# eth_100base-tx_rtl8152b.net
KiCad netlist of a schematic drawn in Altium Designer
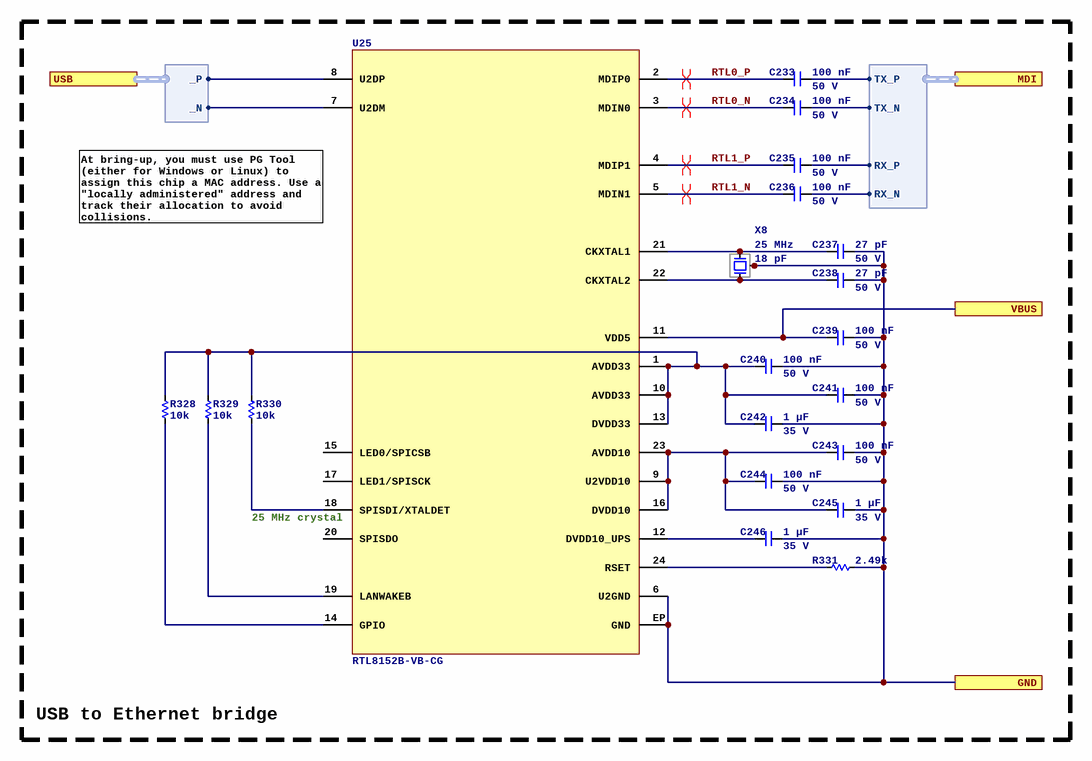
[diagram p0: eth_100base-tx_rtl8152b.SchDoc]

(export (version "E")
  (design (tool "Eeschema 10.0.6"))
  (components
    (comp (ref "C233")
      (value "CL05B104KB54PNC")
      (footprint "C0402")
      (fields
        (field (name "CAPACITANCE") "100 nF")
        (field (name "MANUFACTURER") "Samsung Electro-Mechanics")
        (field (name "VOLTAGE RATING") "50 V")
      )
      (libsource (lib "database") (part "__template_cap"))
    )
    (comp (ref "C234")
      (value "CL05B104KB54PNC")
      (footprint "C0402")
      (fields
        (field (name "CAPACITANCE") "100 nF")
        (field (name "MANUFACTURER") "Samsung Electro-Mechanics")
        (field (name "VOLTAGE RATING") "50 V")
      )
      (libsource (lib "database") (part "__template_cap"))
    )
    (comp (ref "C235")
      (value "CL05B104KB54PNC")
      (footprint "C0402")
      (fields
        (field (name "CAPACITANCE") "100 nF")
        (field (name "MANUFACTURER") "Samsung Electro-Mechanics")
        (field (name "VOLTAGE RATING") "50 V")
      )
      (libsource (lib "database") (part "__template_cap"))
    )
    (comp (ref "C236")
      (value "CL05B104KB54PNC")
      (footprint "C0402")
      (fields
        (field (name "CAPACITANCE") "100 nF")
        (field (name "MANUFACTURER") "Samsung Electro-Mechanics")
        (field (name "VOLTAGE RATING") "50 V")
      )
      (libsource (lib "database") (part "__template_cap"))
    )
    (comp (ref "C237")
      (value "CC0402JRNPO9BN270")
      (footprint "C0402")
      (fields
        (field (name "CAPACITANCE") "27 pF")
        (field (name "MANUFACTURER") "YAGEO")
        (field (name "VOLTAGE RATING") "50 V")
      )
      (libsource (lib "database") (part "__template_cap"))
    )
    (comp (ref "C238")
      (value "CC0402JRNPO9BN270")
      (footprint "C0402")
      (fields
        (field (name "CAPACITANCE") "27 pF")
        (field (name "MANUFACTURER") "YAGEO")
        (field (name "VOLTAGE RATING") "50 V")
      )
      (libsource (lib "database") (part "__template_cap"))
    )
    (comp (ref "C239")
      (value "CL05B104KB54PNC")
      (footprint "C0402")
      (fields
        (field (name "CAPACITANCE") "100 nF")
        (field (name "MANUFACTURER") "Samsung Electro-Mechanics")
        (field (name "VOLTAGE RATING") "50 V")
      )
      (libsource (lib "database") (part "__template_cap"))
    )
    (comp (ref "C240")
      (value "CL05B104KB54PNC")
      (footprint "C0402")
      (fields
        (field (name "CAPACITANCE") "100 nF")
        (field (name "MANUFACTURER") "Samsung Electro-Mechanics")
        (field (name "VOLTAGE RATING") "50 V")
      )
      (libsource (lib "database") (part "__template_cap"))
    )
    (comp (ref "C241")
      (value "CL05B104KB54PNC")
      (footprint "C0402")
      (fields
        (field (name "CAPACITANCE") "100 nF")
        (field (name "MANUFACTURER") "Samsung Electro-Mechanics")
        (field (name "VOLTAGE RATING") "50 V")
      )
      (libsource (lib "database") (part "__template_cap"))
    )
    (comp (ref "C242")
      (value "GMK107AB7105KAHT")
      (footprint "C0603")
      (fields
        (field (name "CAPACITANCE") "1 µF")
        (field (name "MANUFACTURER") "Taiyo Yuden")
        (field (name "VOLTAGE RATING") "35 V")
      )
      (libsource (lib "database") (part "__template_cap"))
    )
    (comp (ref "C243")
      (value "CL05B104KB54PNC")
      (footprint "C0402")
      (fields
        (field (name "CAPACITANCE") "100 nF")
        (field (name "MANUFACTURER") "Samsung Electro-Mechanics")
        (field (name "VOLTAGE RATING") "50 V")
      )
      (libsource (lib "database") (part "__template_cap"))
    )
    (comp (ref "C244")
      (value "CL05B104KB54PNC")
      (footprint "C0402")
      (fields
        (field (name "CAPACITANCE") "100 nF")
        (field (name "MANUFACTURER") "Samsung Electro-Mechanics")
        (field (name "VOLTAGE RATING") "50 V")
      )
      (libsource (lib "database") (part "__template_cap"))
    )
    (comp (ref "C245")
      (value "GMK107AB7105KAHT")
      (footprint "C0603")
      (fields
        (field (name "CAPACITANCE") "1 µF")
        (field (name "MANUFACTURER") "Taiyo Yuden")
        (field (name "VOLTAGE RATING") "35 V")
      )
      (libsource (lib "database") (part "__template_cap"))
    )
    (comp (ref "C246")
      (value "GMK107AB7105KAHT")
      (footprint "C0603")
      (fields
        (field (name "CAPACITANCE") "1 µF")
        (field (name "MANUFACTURER") "Taiyo Yuden")
        (field (name "VOLTAGE RATING") "35 V")
      )
      (libsource (lib "database") (part "__template_cap"))
    )
    (comp (ref "R328")
      (value "10k")
      (footprint "R0402")
      (fields
        (field (name "TOLERANCE") "1%")
        (field (name "MANUFACTURER PART NUMBER") "0402WGF1002TCE")
        (field (name "MANUFACTURER") "UNI-ROYAL(Uniroyal Elec)")
      )
      (libsource (lib "database") (part "__template_resistor"))
    )
    (comp (ref "R329")
      (value "10k")
      (footprint "R0402")
      (fields
        (field (name "TOLERANCE") "1%")
        (field (name "MANUFACTURER PART NUMBER") "0402WGF1002TCE")
        (field (name "MANUFACTURER") "UNI-ROYAL(Uniroyal Elec)")
      )
      (libsource (lib "database") (part "__template_resistor"))
    )
    (comp (ref "R330")
      (value "10k")
      (footprint "R0402")
      (fields
        (field (name "TOLERANCE") "1%")
        (field (name "MANUFACTURER PART NUMBER") "0402WGF1002TCE")
        (field (name "MANUFACTURER") "UNI-ROYAL(Uniroyal Elec)")
      )
      (libsource (lib "database") (part "__template_resistor"))
    )
    (comp (ref "R331")
      (value "2.49k")
      (footprint "R0402")
      (fields
        (field (name "TOLERANCE") "1%")
        (field (name "MANUFACTURER PART NUMBER") "0402WGF2491TCE")
        (field (name "MANUFACTURER") "UNI-ROYAL(Uniroyal Elec)")
      )
      (libsource (lib "database") (part "__template_resistor"))
    )
    (comp (ref "U25")
      (value "RTL8152B-VB-CG")
      (footprint "24QFN4E")
      (description "Integrated 10/100M Ethernet Controller for USB Applications")
      (fields (field (name "MANUFACTURER") "REALTEK"))
      (libsource (lib "database") (part "RTL8152B-VB-CG"))
    )
    (comp (ref "X8")
      (value "ECS-250-18-33-JGN-TR3")
      (footprint "4_SMD_3.2X2.5MM")
      (description "25 MHz ±20ppm Crystal 18pF 40 Ohms 4-SMD, No Lead")
      (fields
        (field (name "MANUFACTURER") "ECS Inc.")
        (field (name "FREQUENCY") "25 MHz")
        (field (name "CAPACITANCE") "18 pF")
      )
      (libsource (lib "database") (part "__template_crystal_4pin"))
    )
  )
  (nets
    (net (code "3") (name "/GND") (class "Default")
      (node (ref "C237") (pin "2") (pintype "passive"))
      (node (ref "C238") (pin "2") (pintype "passive"))
      (node (ref "C239") (pin "1") (pintype "passive"))
      (node (ref "C240") (pin "1") (pintype "passive"))
      (node (ref "C241") (pin "1") (pintype "passive"))
      (node (ref "C242") (pin "2") (pintype "passive"))
      (node (ref "C243") (pin "1") (pintype "passive"))
      (node (ref "C244") (pin "1") (pintype "passive"))
      (node (ref "C245") (pin "2") (pintype "passive"))
      (node (ref "C246") (pin "2") (pintype "passive"))
      (node (ref "R331") (pin "1") (pintype "passive"))
      (node (ref "U25") (pin "6") (pinfunction "U2GND_6") (pintype "passive"))
      (node (ref "U25") (pin "EP") (pinfunction "GND_EP") (pintype "passive"))
      (node (ref "X8") (pin "2") (pinfunction "2_2") (pintype "passive"))
      (node (ref "X8") (pin "4") (pinfunction "4_4") (pintype "passive"))
    )
    (net (code "4") (name "/RTL0_N") (class "Default")
      (node (ref "C234") (pin "2") (pintype "passive"))
      (node (ref "U25") (pin "3") (pinfunction "MDIN0_3") (pintype "passive"))
    )
    (net (code "5") (name "/RTL0_P") (class "Default")
      (node (ref "C233") (pin "2") (pintype "passive"))
      (node (ref "U25") (pin "2") (pinfunction "MDIP0_2") (pintype "passive"))
    )
    (net (code "6") (name "/RTL1_N") (class "Default")
      (node (ref "C236") (pin "2") (pintype "passive"))
      (node (ref "U25") (pin "5") (pinfunction "MDIN1_5") (pintype "passive"))
    )
    (net (code "7") (name "/RTL1_P") (class "Default")
      (node (ref "C235") (pin "2") (pintype "passive"))
      (node (ref "U25") (pin "4") (pinfunction "MDIP1_4") (pintype "passive"))
    )
    (net (code "8") (name "/RX_N") (class "Default") (node (ref "C236") (pin "1") (pintype "passive")))
    (net (code "9") (name "/RX_P") (class "Default") (node (ref "C235") (pin "1") (pintype "passive")))
    (net (code "10") (name "/TX_N") (class "Default") (node (ref "C234") (pin "1") (pintype "passive")))
    (net (code "11") (name "/TX_P") (class "Default") (node (ref "C233") (pin "1") (pintype "passive")))
    (net (code "12") (name "/VBUS") (class "Default")
      (node (ref "C239") (pin "2") (pintype "passive"))
      (node (ref "U25") (pin "11") (pinfunction "VDD5_11") (pintype "passive"))
    )
    (net (code "13") (name "/_N") (class "Default")
      (node (ref "U25") (pin "7") (pinfunction "U2DM_7") (pintype "passive"))
    )
    (net (code "14") (name "/_P") (class "Default")
      (node (ref "U25") (pin "8") (pinfunction "U2DP_8") (pintype "passive"))
    )
    (net (code "17") (name "Net-(U25-AVDD10)") (class "Default")
      (node (ref "C243") (pin "2") (pintype "passive"))
      (node (ref "C244") (pin "2") (pintype "passive"))
      (node (ref "C245") (pin "1") (pintype "passive"))
      (node (ref "U25") (pin "16") (pinfunction "DVDD10_16") (pintype "passive"))
      (node (ref "U25") (pin "23") (pinfunction "AVDD10_23") (pintype "passive"))
      (node (ref "U25") (pin "9") (pinfunction "U2VDD10_9") (pintype "passive"))
    )
    (net (code "18") (name "Net-(U25-CKXTAL1)") (class "Default")
      (node (ref "C237") (pin "1") (pintype "passive"))
      (node (ref "U25") (pin "21") (pinfunction "CKXTAL1_21") (pintype "passive"))
      (node (ref "X8") (pin "3") (pinfunction "3_3") (pintype "passive"))
    )
    (net (code "19") (name "Net-(U25-CKXTAL2)") (class "Default")
      (node (ref "C238") (pin "1") (pintype "passive"))
      (node (ref "U25") (pin "22") (pinfunction "CKXTAL2_22") (pintype "passive"))
      (node (ref "X8") (pin "1") (pinfunction "1_1") (pintype "passive"))
    )
    (net (code "20") (name "Net-(U25-DVDD10_UPS)") (class "Default")
      (node (ref "C246") (pin "1") (pintype "passive"))
      (node (ref "U25") (pin "12") (pinfunction "DVDD10_UPS_12") (pintype "passive"))
    )
    (net (code "21") (name "Net-(U25-DVDD33)") (class "Default")
      (node (ref "C240") (pin "2") (pintype "passive"))
      (node (ref "C241") (pin "2") (pintype "passive"))
      (node (ref "C242") (pin "1") (pintype "passive"))
      (node (ref "R328") (pin "1") (pintype "passive"))
      (node (ref "R329") (pin "1") (pintype "passive"))
      (node (ref "R330") (pin "1") (pintype "passive"))
      (node (ref "U25") (pin "1") (pinfunction "AVDD33_1") (pintype "passive"))
      (node (ref "U25") (pin "10") (pinfunction "AVDD33_10") (pintype "passive"))
      (node (ref "U25") (pin "13") (pinfunction "DVDD33_13") (pintype "passive"))
    )
    (net (code "22") (name "Net-(U25-GPIO)") (class "Default")
      (node (ref "R328") (pin "2") (pintype "passive"))
      (node (ref "U25") (pin "14") (pinfunction "GPIO_14") (pintype "passive"))
    )
    (net (code "23") (name "Net-(U25-LANWAKEB)") (class "Default")
      (node (ref "R329") (pin "2") (pintype "passive"))
      (node (ref "U25") (pin "19") (pinfunction "LANWAKEB_19") (pintype "passive"))
    )
    (net (code "24") (name "Net-(U25-RSET)") (class "Default")
      (node (ref "R331") (pin "2") (pintype "passive"))
      (node (ref "U25") (pin "24") (pinfunction "RSET_24") (pintype "passive"))
    )
    (net (code "25") (name "Net-(U25-SPISDI{slash}XTALDET)") (class "Default")
      (node (ref "R330") (pin "2") (pintype "passive"))
      (node (ref "U25") (pin "18") (pinfunction "SPISDI/XTALDET_18") (pintype "passive"))
    )
    (net (code "26") (name "unconnected-(U25-LED0{slash}SPICSB-Pad15)") (class "Default")
      (node (ref "U25") (pin "15") (pinfunction "LED0/SPICSB_15") (pintype "passive"))
    )
    (net (code "27") (name "unconnected-(U25-LED1{slash}SPISCK-Pad17)") (class "Default")
      (node (ref "U25") (pin "17") (pinfunction "LED1/SPISCK_17") (pintype "passive"))
    )
    (net (code "28") (name "unconnected-(U25-SPISDO-Pad20)") (class "Default")
      (node (ref "U25") (pin "20") (pinfunction "SPISDO_20") (pintype "passive"))
    )
  )
)
